# AC_Grid.net
KiCad netlist of a schematic drawn in Altium Designer
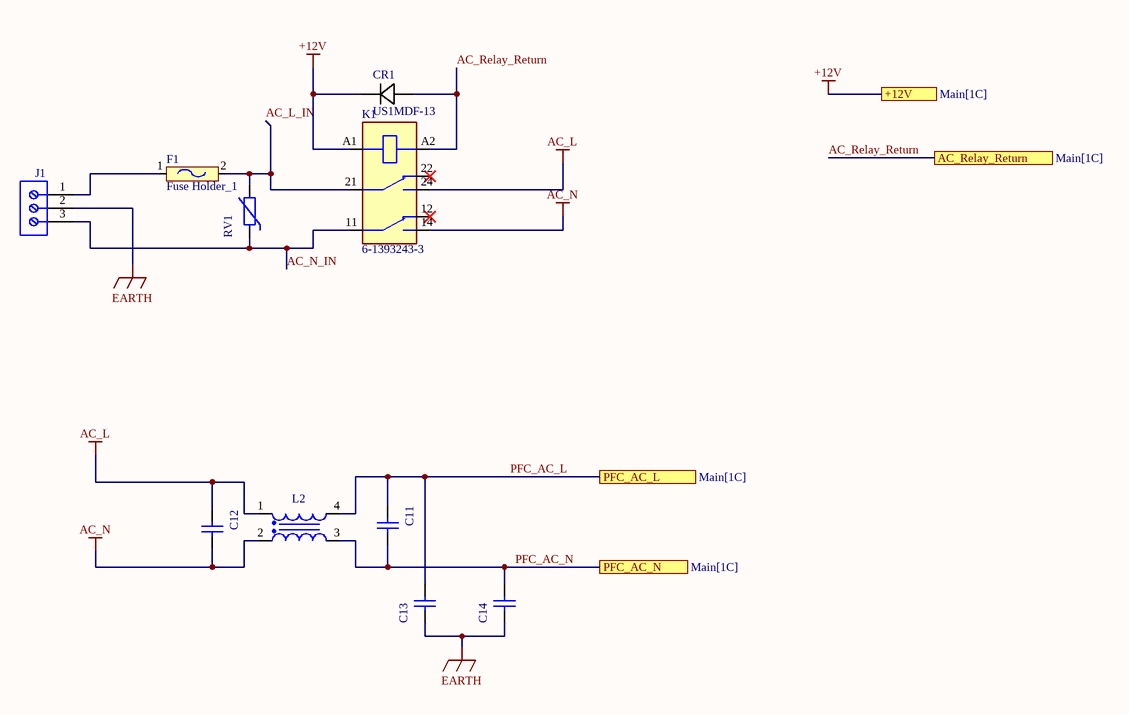
[diagram p0: AC_Grid.SchDoc]

(export (version "E")
  (design (tool "Eeschema 10.0.6"))
  (components
    (comp (ref "C11")
      (value "1µF")
      (footprint "WCAP-FTBE_L26W9H18")
      (description "WCAP-FTBE Film Capacitor, THT, L26 x W9 x H18mm, 1µF, 400V")
      (fields
        (field (name "MANUFACTURER PART NUMBER") "890283426008CS")
        (field (name "MANUFACTURER") "Wurth Elektronik")
      )
      (libsource (lib "WE - Passive Components") (part "Capacitor_Non-Polarized"))
    )
    (comp (ref "C12")
      (value "1µF")
      (footprint "WCAP-FTBE_L26W9H18")
      (description "WCAP-FTBE Film Capacitor, THT, L26 x W9 x H18mm, 1µF, 400V")
      (fields
        (field (name "MANUFACTURER PART NUMBER") "890283426008CS")
        (field (name "MANUFACTURER") "Wurth Elektronik")
      )
      (libsource (lib "WE - Passive Components") (part "Capacitor_Non-Polarized"))
    )
    (comp (ref "C13")
      (value "470 pF")
      (footprint "WCAP-CSSA_1812_8853522110011")
      (fields
        (field (name "MANUFACTURER PART NUMBER") "8853522110011")
        (field (name "MANUFACTURER") "Wurth Elektronik")
      )
      (libsource (lib "WE - Passive Components") (part "Capacitor_Non-Polarized"))
    )
    (comp (ref "C14")
      (value "470 pF")
      (footprint "WCAP-CSSA_1812_8853522110011")
      (fields
        (field (name "MANUFACTURER PART NUMBER") "8853522110011")
        (field (name "MANUFACTURER") "Wurth Elektronik")
      )
      (libsource (lib "WE - Passive Components") (part "Capacitor_Non-Polarized"))
    )
    (comp (ref "CR1")
      (value "US1MDF-13")
      (footprint "DIODE_US1MDF-13_DIO-M")
      (description "No Description Available")
      (fields (field (name "COPYRIGHT") "Copyright (C) 2021 Ultra Librarian. All rights reserved."))
      (libsource (lib "Schlib1") (part "US1MDF-13"))
    )
    (comp (ref "F1")
      (value "Fuse Holder_1")
      (footprint "Fuse Holder")
      (libsource (lib "Schlib1") (part "Fuse Holder_1"))
    )
    (comp (ref "J1")
      (value "691250610003")
      (footprint "691250610003")
      (description "WR-TBL Series 2506 Horizontal Entry Modular, THT, pitch 6.35mm, 03p")
      (fields (field (name "MANUFACTURER") "Wurth Elektronik"))
      (libsource (lib "WE - Electromechanical Components") (part "TBL - 1R - 03P - Screw"))
    )
    (comp (ref "K1")
      (value "6-1393243-3")
      (footprint "RELAY_6-1393243-3")
      (description "General Purpose Relay DPDT (2 Form C) 12VDC Coil Through Hole")
      (fields (field (name "MF") "TE Connectivity"))
      (libsource (lib "Schlib1") (part "6-1393243-3"))
    )
    (comp (ref "L2")
      (value "1.7mH")
      (footprint "WE-CMB HV_Type XL_744830017132")
      (description "WE-CMB HV Common Mode Power Line Choke, THT, Type XL, 1.7mH, 13.2A, 10mOhm")
      (fields
        (field (name "MANUFACTURER PART NUMBER") "744830017132")
        (field (name "MANUFACTURER") "Wurth Elektronik")
      )
      (libsource (lib "WE - Passive Components") (part "WE-CMB HV"))
    )
    (comp (ref "RV1")
      (value "275Vrms, 350Vdc")
      (footprint "D16.5W6.7H20P1.3")
      (description "WE-VD Disk Varistor, THT, D16.5mm x H20mm, 275Vrms, 350Vdc, 4500A, 132J")
      (fields
        (field (name "MANUFACTURER PART NUMBER") "820542711")
        (field (name "MANUFACTURER") "Wurth Elektronik")
      )
      (libsource (lib "WE - Passive Components") (part "Varistor"))
    )
  )
  (nets
    (net (code "1") (name "+12V") (class "Default")
      (node (ref "CR1") (pin "1") (pinfunction "1_1") (pintype "passive"))
      (node (ref "K1") (pin "A1") (pinfunction "A1_A1") (pintype "passive"))
    )
    (net (code "2") (name "/AC_L_IN") (class "Default")
      (node (ref "F1") (pin "2") (pinfunction "VCC26_2") (pintype "passive"))
      (node (ref "K1") (pin "21") (pinfunction "21_21") (pintype "passive"))
      (node (ref "RV1") (pin "2") (pinfunction "2_2") (pintype "passive"))
    )
    (net (code "3") (name "/AC_N_IN") (class "Default")
      (node (ref "J1") (pin "3") (pinfunction "3_3") (pintype "passive"))
      (node (ref "K1") (pin "11") (pinfunction "11_11") (pintype "passive"))
      (node (ref "RV1") (pin "1") (pinfunction "1_1") (pintype "passive"))
    )
    (net (code "4") (name "/AC_Relay_Return") (class "Default")
      (node (ref "CR1") (pin "2") (pinfunction "2_2") (pintype "passive"))
      (node (ref "K1") (pin "A2") (pinfunction "A2_A2") (pintype "passive"))
    )
    (net (code "5") (name "/PFC_AC_L") (class "Default")
      (node (ref "C11") (pin "1") (pinfunction "1_1") (pintype "passive"))
      (node (ref "C13") (pin "2") (pinfunction "2_2") (pintype "passive"))
      (node (ref "L2") (pin "4") (pinfunction "4_4") (pintype "passive"))
    )
    (net (code "6") (name "/PFC_AC_N") (class "Default")
      (node (ref "C11") (pin "2") (pinfunction "2_2") (pintype "passive"))
      (node (ref "C14") (pin "2") (pinfunction "2_2") (pintype "passive"))
      (node (ref "L2") (pin "3") (pinfunction "3_3") (pintype "passive"))
    )
    (net (code "7") (name "AC_L") (class "Default")
      (node (ref "C12") (pin "1") (pinfunction "1_1") (pintype "passive"))
      (node (ref "K1") (pin "24") (pinfunction "24_24") (pintype "passive"))
      (node (ref "L2") (pin "1") (pinfunction "1_1") (pintype "passive"))
    )
    (net (code "8") (name "AC_N") (class "Default")
      (node (ref "C12") (pin "2") (pinfunction "2_2") (pintype "passive"))
      (node (ref "K1") (pin "14") (pinfunction "14_14") (pintype "passive"))
      (node (ref "L2") (pin "2") (pinfunction "2_2") (pintype "passive"))
    )
    (net (code "9") (name "EARTH") (class "Default")
      (node (ref "C13") (pin "1") (pinfunction "1_1") (pintype "passive"))
      (node (ref "C14") (pin "1") (pinfunction "1_1") (pintype "passive"))
      (node (ref "J1") (pin "2") (pinfunction "2_2") (pintype "passive"))
    )
    (net (code "10") (name "Net-(F1-VCC27)") (class "Default")
      (node (ref "F1") (pin "1") (pinfunction "VCC27_1") (pintype "passive"))
      (node (ref "J1") (pin "1") (pinfunction "1_1") (pintype "passive"))
    )
    (net (code "11") (name "unconnected-(K1-Pad12)") (class "Default")
      (node (ref "K1") (pin "12") (pinfunction "12_12") (pintype "passive+no_connect"))
    )
    (net (code "12") (name "unconnected-(K1-Pad22)") (class "Default")
      (node (ref "K1") (pin "22") (pinfunction "22_22") (pintype "passive+no_connect"))
    )
  )
)
